# Clock_management.net
KiCad netlist of a schematic drawn in Altium Designer
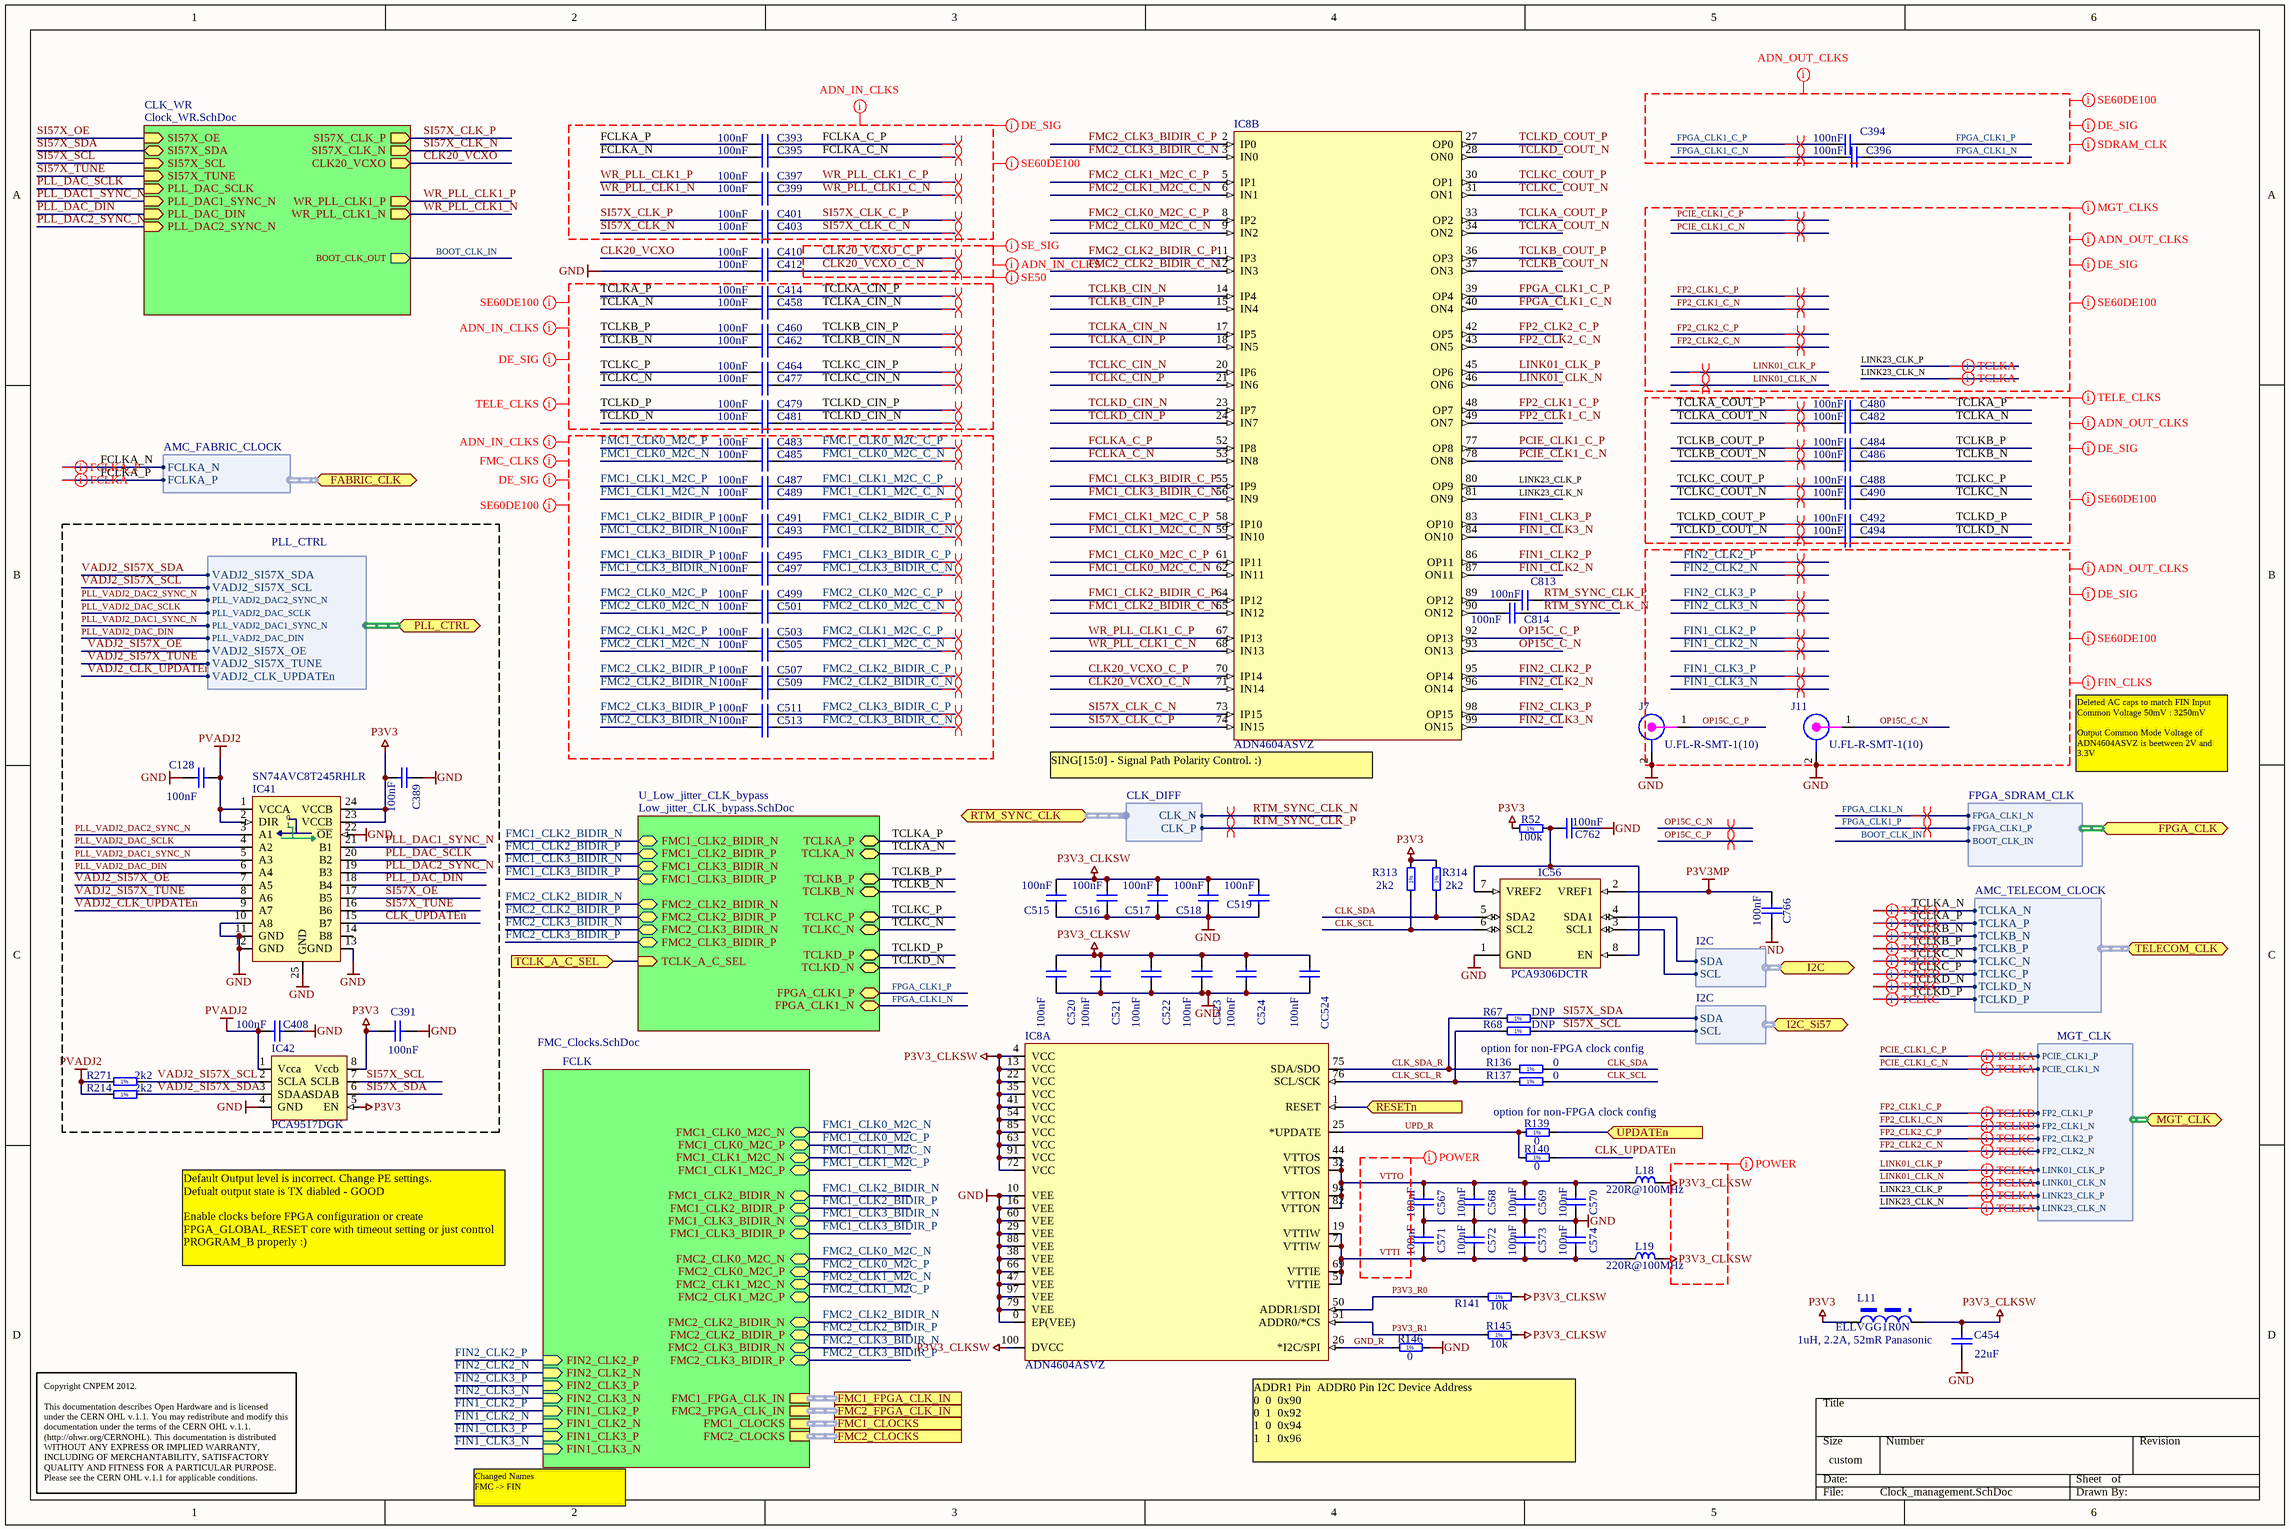
[diagram p0: Clock_management.SchDoc]

(export (version "E")
  (design (tool "Eeschema 10.0.6"))
  (components
    (comp (ref "C128")
      (value "100nF")
      (footprint "CAPC0603X33N")
      (description "Non-polarised capacitor")
      (fields
        (field (name "PART NUMBER") "CC0201_100NF_6.3V_10%_X5R")
        (field (name "VOLTAGE") "6.3V")
        (field (name "AUTHOR") "CERN DEM JLC")
      )
      (libsource (lib "Capacitors") (part "Capacitor - non polarized"))
    )
    (comp (ref "C389")
      (value "100nF")
      (footprint "CAPC0603X33N")
      (description "Non-polarised capacitor")
      (fields
        (field (name "PART NUMBER") "CC0201_100NF_6.3V_10%_X5R")
        (field (name "VOLTAGE") "6.3V")
        (field (name "AUTHOR") "CERN DEM JLC")
      )
      (libsource (lib "Capacitors") (part "Capacitor - non polarized"))
    )
    (comp (ref "C391")
      (value "100nF")
      (footprint "CAPC0603X33N")
      (description "Non-polarised capacitor")
      (fields
        (field (name "PART NUMBER") "CC0201_100NF_6.3V_10%_X5R")
        (field (name "VOLTAGE") "6.3V")
        (field (name "AUTHOR") "CERN DEM JLC")
      )
      (libsource (lib "Capacitors") (part "Capacitor - non polarized"))
    )
    (comp (ref "C393")
      (value "100nF")
      (footprint "CAPC0603X33N")
      (description "Non-polarised capacitor")
      (fields
        (field (name "PART NUMBER") "CC0201_100NF_6.3V_10%_X5R")
        (field (name "VOLTAGE") "6.3V")
        (field (name "AUTHOR") "CERN DEM JLC")
      )
      (libsource (lib "Capacitors") (part "Capacitor - non polarized"))
    )
    (comp (ref "C394")
      (value "100nF")
      (footprint "CAPC0603X33N")
      (description "Non-polarised capacitor")
      (fields
        (field (name "PART NUMBER") "CC0201_100NF_6.3V_10%_X5R")
        (field (name "VOLTAGE") "6.3V")
        (field (name "AUTHOR") "CERN DEM JLC")
      )
      (libsource (lib "Capacitors") (part "Capacitor - non polarized"))
    )
    (comp (ref "C395")
      (value "100nF")
      (footprint "CAPC0603X33N")
      (description "Non-polarised capacitor")
      (fields
        (field (name "PART NUMBER") "CC0201_100NF_6.3V_10%_X5R")
        (field (name "VOLTAGE") "6.3V")
        (field (name "AUTHOR") "CERN DEM JLC")
      )
      (libsource (lib "Capacitors") (part "Capacitor - non polarized"))
    )
    (comp (ref "C396")
      (value "100nF")
      (footprint "CAPC0603X33N")
      (description "Non-polarised capacitor")
      (fields
        (field (name "PART NUMBER") "CC0201_100NF_6.3V_10%_X5R")
        (field (name "VOLTAGE") "6.3V")
        (field (name "AUTHOR") "CERN DEM JLC")
      )
      (libsource (lib "Capacitors") (part "Capacitor - non polarized"))
    )
    (comp (ref "C397")
      (value "100nF")
      (footprint "CAPC0603X33N")
      (description "Non-polarised capacitor")
      (fields
        (field (name "PART NUMBER") "CC0201_100NF_6.3V_10%_X5R")
        (field (name "VOLTAGE") "6.3V")
        (field (name "AUTHOR") "CERN DEM JLC")
      )
      (libsource (lib "Capacitors") (part "Capacitor - non polarized"))
    )
    (comp (ref "C399")
      (value "100nF")
      (footprint "CAPC0603X33N")
      (description "Non-polarised capacitor")
      (fields
        (field (name "PART NUMBER") "CC0201_100NF_6.3V_10%_X5R")
        (field (name "VOLTAGE") "6.3V")
        (field (name "AUTHOR") "CERN DEM JLC")
      )
      (libsource (lib "Capacitors") (part "Capacitor - non polarized"))
    )
    (comp (ref "C401")
      (value "100nF")
      (footprint "CAPC0603X33N")
      (description "Non-polarised capacitor")
      (fields
        (field (name "PART NUMBER") "CC0201_100NF_6.3V_10%_X5R")
        (field (name "VOLTAGE") "6.3V")
        (field (name "AUTHOR") "CERN DEM JLC")
      )
      (libsource (lib "Capacitors") (part "Capacitor - non polarized"))
    )
    (comp (ref "C403")
      (value "100nF")
      (footprint "CAPC0603X33N")
      (description "Non-polarised capacitor")
      (fields
        (field (name "PART NUMBER") "CC0201_100NF_6.3V_10%_X5R")
        (field (name "VOLTAGE") "6.3V")
        (field (name "AUTHOR") "CERN DEM JLC")
      )
      (libsource (lib "Capacitors") (part "Capacitor - non polarized"))
    )
    (comp (ref "C408")
      (value "100nF")
      (footprint "CAPC0603X33N")
      (description "Non-polarised capacitor")
      (fields
        (field (name "PART NUMBER") "CC0201_100NF_6.3V_10%_X5R")
        (field (name "VOLTAGE") "6.3V")
        (field (name "AUTHOR") "CERN DEM JLC")
      )
      (libsource (lib "Capacitors") (part "Capacitor - non polarized"))
    )
    (comp (ref "C410")
      (value "100nF")
      (footprint "CAPC0603X33N")
      (description "Non-polarised capacitor")
      (fields
        (field (name "PART NUMBER") "CC0201_100NF_6.3V_10%_X5R")
        (field (name "VOLTAGE") "6.3V")
        (field (name "AUTHOR") "CERN DEM JLC")
      )
      (libsource (lib "Capacitors") (part "Capacitor - non polarized"))
    )
    (comp (ref "C412")
      (value "100nF")
      (footprint "CAPC0603X33N")
      (description "Non-polarised capacitor")
      (fields
        (field (name "PART NUMBER") "CC0201_100NF_6.3V_10%_X5R")
        (field (name "VOLTAGE") "6.3V")
        (field (name "AUTHOR") "CERN DEM JLC")
      )
      (libsource (lib "Capacitors") (part "Capacitor - non polarized"))
    )
    (comp (ref "C414")
      (value "100nF")
      (footprint "CAPC0603X33N")
      (description "Non-polarised capacitor")
      (fields
        (field (name "PART NUMBER") "CC0201_100NF_6.3V_10%_X5R")
        (field (name "VOLTAGE") "6.3V")
        (field (name "AUTHOR") "CERN DEM JLC")
      )
      (libsource (lib "Capacitors") (part "Capacitor - non polarized"))
    )
    (comp (ref "C454")
      (value "22uF")
      (footprint "CAPC3216X180N")
      (description "Non-polarised capacitor")
      (fields
        (field (name "PART NUMBER") "CC1206_22UF_10V_10%_X7R")
        (field (name "VOLTAGE") "10V")
        (field (name "AUTHOR") "CERN DEM JLC")
      )
      (libsource (lib "Capacitors") (part "Capacitor - non polarized"))
    )
    (comp (ref "C458")
      (value "100nF")
      (footprint "CAPC0603X33N")
      (description "Non-polarised capacitor")
      (fields
        (field (name "PART NUMBER") "CC0201_100NF_6.3V_10%_X5R")
        (field (name "VOLTAGE") "6.3V")
        (field (name "AUTHOR") "CERN DEM JLC")
      )
      (libsource (lib "Capacitors") (part "Capacitor - non polarized"))
    )
    (comp (ref "C460")
      (value "100nF")
      (footprint "CAPC0603X33N")
      (description "Non-polarised capacitor")
      (fields
        (field (name "PART NUMBER") "CC0201_100NF_6.3V_10%_X5R")
        (field (name "VOLTAGE") "6.3V")
        (field (name "AUTHOR") "CERN DEM JLC")
      )
      (libsource (lib "Capacitors") (part "Capacitor - non polarized"))
    )
    (comp (ref "C462")
      (value "100nF")
      (footprint "CAPC0603X33N")
      (description "Non-polarised capacitor")
      (fields
        (field (name "PART NUMBER") "CC0201_100NF_6.3V_10%_X5R")
        (field (name "VOLTAGE") "6.3V")
        (field (name "AUTHOR") "CERN DEM JLC")
      )
      (libsource (lib "Capacitors") (part "Capacitor - non polarized"))
    )
    (comp (ref "C464")
      (value "100nF")
      (footprint "CAPC0603X33N")
      (description "Non-polarised capacitor")
      (fields
        (field (name "PART NUMBER") "CC0201_100NF_6.3V_10%_X5R")
        (field (name "VOLTAGE") "6.3V")
        (field (name "AUTHOR") "CERN DEM JLC")
      )
      (libsource (lib "Capacitors") (part "Capacitor - non polarized"))
    )
    (comp (ref "C477")
      (value "100nF")
      (footprint "CAPC0603X33N")
      (description "Non-polarised capacitor")
      (fields
        (field (name "PART NUMBER") "CC0201_100NF_6.3V_10%_X5R")
        (field (name "VOLTAGE") "6.3V")
        (field (name "AUTHOR") "CERN DEM JLC")
      )
      (libsource (lib "Capacitors") (part "Capacitor - non polarized"))
    )
    (comp (ref "C479")
      (value "100nF")
      (footprint "CAPC0603X33N")
      (description "Non-polarised capacitor")
      (fields
        (field (name "PART NUMBER") "CC0201_100NF_6.3V_10%_X5R")
        (field (name "VOLTAGE") "6.3V")
        (field (name "AUTHOR") "CERN DEM JLC")
      )
      (libsource (lib "Capacitors") (part "Capacitor - non polarized"))
    )
    (comp (ref "C480")
      (value "100nF")
      (footprint "CAPC0603X33N")
      (description "Non-polarised capacitor")
      (fields
        (field (name "PART NUMBER") "CC0201_100NF_6.3V_10%_X5R")
        (field (name "VOLTAGE") "6.3V")
        (field (name "AUTHOR") "CERN DEM JLC")
      )
      (libsource (lib "Capacitors") (part "Capacitor - non polarized"))
    )
    (comp (ref "C481")
      (value "100nF")
      (footprint "CAPC0603X33N")
      (description "Non-polarised capacitor")
      (fields
        (field (name "PART NUMBER") "CC0201_100NF_6.3V_10%_X5R")
        (field (name "VOLTAGE") "6.3V")
        (field (name "AUTHOR") "CERN DEM JLC")
      )
      (libsource (lib "Capacitors") (part "Capacitor - non polarized"))
    )
    (comp (ref "C482")
      (value "100nF")
      (footprint "CAPC0603X33N")
      (description "Non-polarised capacitor")
      (fields
        (field (name "PART NUMBER") "CC0201_100NF_6.3V_10%_X5R")
        (field (name "VOLTAGE") "6.3V")
        (field (name "AUTHOR") "CERN DEM JLC")
      )
      (libsource (lib "Capacitors") (part "Capacitor - non polarized"))
    )
    (comp (ref "C483")
      (value "100nF")
      (footprint "CAPC0603X33N")
      (description "Non-polarised capacitor")
      (fields
        (field (name "PART NUMBER") "CC0201_100NF_6.3V_10%_X5R")
        (field (name "VOLTAGE") "6.3V")
        (field (name "AUTHOR") "CERN DEM JLC")
      )
      (libsource (lib "Capacitors") (part "Capacitor - non polarized"))
    )
    (comp (ref "C484")
      (value "100nF")
      (footprint "CAPC0603X33N")
      (description "Non-polarised capacitor")
      (fields
        (field (name "PART NUMBER") "CC0201_100NF_6.3V_10%_X5R")
        (field (name "VOLTAGE") "6.3V")
        (field (name "AUTHOR") "CERN DEM JLC")
      )
      (libsource (lib "Capacitors") (part "Capacitor - non polarized"))
    )
    (comp (ref "C485")
      (value "100nF")
      (footprint "CAPC0603X33N")
      (description "Non-polarised capacitor")
      (fields
        (field (name "PART NUMBER") "CC0201_100NF_6.3V_10%_X5R")
        (field (name "VOLTAGE") "6.3V")
        (field (name "AUTHOR") "CERN DEM JLC")
      )
      (libsource (lib "Capacitors") (part "Capacitor - non polarized"))
    )
    (comp (ref "C486")
      (value "100nF")
      (footprint "CAPC0603X33N")
      (description "Non-polarised capacitor")
      (fields
        (field (name "PART NUMBER") "CC0201_100NF_6.3V_10%_X5R")
        (field (name "VOLTAGE") "6.3V")
        (field (name "AUTHOR") "CERN DEM JLC")
      )
      (libsource (lib "Capacitors") (part "Capacitor - non polarized"))
    )
    (comp (ref "C487")
      (value "100nF")
      (footprint "CAPC0603X33N")
      (description "Non-polarised capacitor")
      (fields
        (field (name "PART NUMBER") "CC0201_100NF_6.3V_10%_X5R")
        (field (name "VOLTAGE") "6.3V")
        (field (name "AUTHOR") "CERN DEM JLC")
      )
      (libsource (lib "Capacitors") (part "Capacitor - non polarized"))
    )
    (comp (ref "C488")
      (value "100nF")
      (footprint "CAPC0603X33N")
      (description "Non-polarised capacitor")
      (fields
        (field (name "PART NUMBER") "CC0201_100NF_6.3V_10%_X5R")
        (field (name "VOLTAGE") "6.3V")
        (field (name "AUTHOR") "CERN DEM JLC")
      )
      (libsource (lib "Capacitors") (part "Capacitor - non polarized"))
    )
    (comp (ref "C489")
      (value "100nF")
      (footprint "CAPC0603X33N")
      (description "Non-polarised capacitor")
      (fields
        (field (name "PART NUMBER") "CC0201_100NF_6.3V_10%_X5R")
        (field (name "VOLTAGE") "6.3V")
        (field (name "AUTHOR") "CERN DEM JLC")
      )
      (libsource (lib "Capacitors") (part "Capacitor - non polarized"))
    )
    (comp (ref "C490")
      (value "100nF")
      (footprint "CAPC0603X33N")
      (description "Non-polarised capacitor")
      (fields
        (field (name "PART NUMBER") "CC0201_100NF_6.3V_10%_X5R")
        (field (name "VOLTAGE") "6.3V")
        (field (name "AUTHOR") "CERN DEM JLC")
      )
      (libsource (lib "Capacitors") (part "Capacitor - non polarized"))
    )
    (comp (ref "C491")
      (value "100nF")
      (footprint "CAPC0603X33N")
      (description "Non-polarised capacitor")
      (fields
        (field (name "PART NUMBER") "CC0201_100NF_6.3V_10%_X5R")
        (field (name "VOLTAGE") "6.3V")
        (field (name "AUTHOR") "CERN DEM JLC")
      )
      (libsource (lib "Capacitors") (part "Capacitor - non polarized"))
    )
    (comp (ref "C492")
      (value "100nF")
      (footprint "CAPC0603X33N")
      (description "Non-polarised capacitor")
      (fields
        (field (name "PART NUMBER") "CC0201_100NF_6.3V_10%_X5R")
        (field (name "VOLTAGE") "6.3V")
        (field (name "AUTHOR") "CERN DEM JLC")
      )
      (libsource (lib "Capacitors") (part "Capacitor - non polarized"))
    )
    (comp (ref "C493")
      (value "100nF")
      (footprint "CAPC0603X33N")
      (description "Non-polarised capacitor")
      (fields
        (field (name "PART NUMBER") "CC0201_100NF_6.3V_10%_X5R")
        (field (name "VOLTAGE") "6.3V")
        (field (name "AUTHOR") "CERN DEM JLC")
      )
      (libsource (lib "Capacitors") (part "Capacitor - non polarized"))
    )
    (comp (ref "C494")
      (value "100nF")
      (footprint "CAPC0603X33N")
      (description "Non-polarised capacitor")
      (fields
        (field (name "PART NUMBER") "CC0201_100NF_6.3V_10%_X5R")
        (field (name "VOLTAGE") "6.3V")
        (field (name "AUTHOR") "CERN DEM JLC")
      )
      (libsource (lib "Capacitors") (part "Capacitor - non polarized"))
    )
    (comp (ref "C495")
      (value "100nF")
      (footprint "CAPC0603X33N")
      (description "Non-polarised capacitor")
      (fields
        (field (name "PART NUMBER") "CC0201_100NF_6.3V_10%_X5R")
        (field (name "VOLTAGE") "6.3V")
        (field (name "AUTHOR") "CERN DEM JLC")
      )
      (libsource (lib "Capacitors") (part "Capacitor - non polarized"))
    )
    (comp (ref "C497")
      (value "100nF")
      (footprint "CAPC0603X33N")
      (description "Non-polarised capacitor")
      (fields
        (field (name "PART NUMBER") "CC0201_100NF_6.3V_10%_X5R")
        (field (name "VOLTAGE") "6.3V")
        (field (name "AUTHOR") "CERN DEM JLC")
      )
      (libsource (lib "Capacitors") (part "Capacitor - non polarized"))
    )
    (comp (ref "C499")
      (value "100nF")
      (footprint "CAPC0603X33N")
      (description "Non-polarised capacitor")
      (fields
        (field (name "PART NUMBER") "CC0201_100NF_6.3V_10%_X5R")
        (field (name "VOLTAGE") "6.3V")
        (field (name "AUTHOR") "CERN DEM JLC")
      )
      (libsource (lib "Capacitors") (part "Capacitor - non polarized"))
    )
    (comp (ref "C501")
      (value "100nF")
      (footprint "CAPC0603X33N")
      (description "Non-polarised capacitor")
      (fields
        (field (name "PART NUMBER") "CC0201_100NF_6.3V_10%_X5R")
        (field (name "VOLTAGE") "6.3V")
        (field (name "AUTHOR") "CERN DEM JLC")
      )
      (libsource (lib "Capacitors") (part "Capacitor - non polarized"))
    )
    (comp (ref "C503")
      (value "100nF")
      (footprint "CAPC0603X33N")
      (description "Non-polarised capacitor")
      (fields
        (field (name "PART NUMBER") "CC0201_100NF_6.3V_10%_X5R")
        (field (name "VOLTAGE") "6.3V")
        (field (name "AUTHOR") "CERN DEM JLC")
      )
      (libsource (lib "Capacitors") (part "Capacitor - non polarized"))
    )
    (comp (ref "C505")
      (value "100nF")
      (footprint "CAPC0603X33N")
      (description "Non-polarised capacitor")
      (fields
        (field (name "PART NUMBER") "CC0201_100NF_6.3V_10%_X5R")
        (field (name "VOLTAGE") "6.3V")
        (field (name "AUTHOR") "CERN DEM JLC")
      )
      (libsource (lib "Capacitors") (part "Capacitor - non polarized"))
    )
    (comp (ref "C507")
      (value "100nF")
      (footprint "CAPC0603X33N")
      (description "Non-polarised capacitor")
      (fields
        (field (name "PART NUMBER") "CC0201_100NF_6.3V_10%_X5R")
        (field (name "VOLTAGE") "6.3V")
        (field (name "AUTHOR") "CERN DEM JLC")
      )
      (libsource (lib "Capacitors") (part "Capacitor - non polarized"))
    )
    (comp (ref "C509")
      (value "100nF")
      (footprint "CAPC0603X33N")
      (description "Non-polarised capacitor")
      (fields
        (field (name "PART NUMBER") "CC0201_100NF_6.3V_10%_X5R")
        (field (name "VOLTAGE") "6.3V")
        (field (name "AUTHOR") "CERN DEM JLC")
      )
      (libsource (lib "Capacitors") (part "Capacitor - non polarized"))
    )
    (comp (ref "C511")
      (value "100nF")
      (footprint "CAPC0603X33N")
      (description "Non-polarised capacitor")
      (fields
        (field (name "PART NUMBER") "CC0201_100NF_6.3V_10%_X5R")
        (field (name "VOLTAGE") "6.3V")
        (field (name "AUTHOR") "CERN DEM JLC")
      )
      (libsource (lib "Capacitors") (part "Capacitor - non polarized"))
    )
    (comp (ref "C513")
      (value "100nF")
      (footprint "CAPC0603X33N")
      (description "Non-polarised capacitor")
      (fields
        (field (name "PART NUMBER") "CC0201_100NF_6.3V_10%_X5R")
        (field (name "VOLTAGE") "6.3V")
        (field (name "AUTHOR") "CERN DEM JLC")
      )
      (libsource (lib "Capacitors") (part "Capacitor - non polarized"))
    )
    (comp (ref "C515")
      (value "100nF")
      (footprint "CAPC0603X33N")
      (description "Non-polarised capacitor")
      (fields
        (field (name "PART NUMBER") "CC0201_100NF_6.3V_10%_X5R")
        (field (name "VOLTAGE") "6.3V")
        (field (name "AUTHOR") "CERN DEM JLC")
      )
      (libsource (lib "Capacitors") (part "Capacitor - non polarized"))
    )
    (comp (ref "C516")
      (value "100nF")
      (footprint "CAPC0603X33N")
      (description "Non-polarised capacitor")
      (fields
        (field (name "PART NUMBER") "CC0201_100NF_6.3V_10%_X5R")
        (field (name "VOLTAGE") "6.3V")
        (field (name "AUTHOR") "CERN DEM JLC")
      )
      (libsource (lib "Capacitors") (part "Capacitor - non polarized"))
    )
    (comp (ref "C517")
      (value "100nF")
      (footprint "CAPC0603X33N")
      (description "Non-polarised capacitor")
      (fields
        (field (name "PART NUMBER") "CC0201_100NF_6.3V_10%_X5R")
        (field (name "VOLTAGE") "6.3V")
        (field (name "AUTHOR") "CERN DEM JLC")
      )
      (libsource (lib "Capacitors") (part "Capacitor - non polarized"))
    )
    (comp (ref "C518")
      (value "100nF")
      (footprint "CAPC0603X33N")
      (description "Non-polarised capacitor")
      (fields
        (field (name "PART NUMBER") "CC0201_100NF_6.3V_10%_X5R")
        (field (name "VOLTAGE") "6.3V")
        (field (name "AUTHOR") "CERN DEM JLC")
      )
      (libsource (lib "Capacitors") (part "Capacitor - non polarized"))
    )
    (comp (ref "C519")
      (value "100nF")
      (footprint "CAPC0603X33N")
      (description "Non-polarised capacitor")
      (fields
        (field (name "PART NUMBER") "CC0201_100NF_6.3V_10%_X5R")
        (field (name "VOLTAGE") "6.3V")
        (field (name "AUTHOR") "CERN DEM JLC")
      )
      (libsource (lib "Capacitors") (part "Capacitor - non polarized"))
    )
    (comp (ref "C520")
      (value "100nF")
      (footprint "CAPC0603X33N")
      (description "Non-polarised capacitor")
      (fields
        (field (name "PART NUMBER") "CC0201_100NF_6.3V_10%_X5R")
        (field (name "VOLTAGE") "6.3V")
        (field (name "AUTHOR") "CERN DEM JLC")
      )
      (libsource (lib "Capacitors") (part "Capacitor - non polarized"))
    )
    (comp (ref "C521")
      (value "100nF")
      (footprint "CAPC0603X33N")
      (description "Non-polarised capacitor")
      (fields
        (field (name "PART NUMBER") "CC0201_100NF_6.3V_10%_X5R")
        (field (name "VOLTAGE") "6.3V")
        (field (name "AUTHOR") "CERN DEM JLC")
      )
      (libsource (lib "Capacitors") (part "Capacitor - non polarized"))
    )
    (comp (ref "C522")
      (value "100nF")
      (footprint "CAPC0603X33N")
      (description "Non-polarised capacitor")
      (fields
        (field (name "PART NUMBER") "CC0201_100NF_6.3V_10%_X5R")
        (field (name "VOLTAGE") "6.3V")
        (field (name "AUTHOR") "CERN DEM JLC")
      )
      (libsource (lib "Capacitors") (part "Capacitor - non polarized"))
    )
    (comp (ref "C523")
      (value "100nF")
      (footprint "CAPC0603X33N")
      (description "Non-polarised capacitor")
      (fields
        (field (name "PART NUMBER") "CC0201_100NF_6.3V_10%_X5R")
        (field (name "VOLTAGE") "6.3V")
        (field (name "AUTHOR") "CERN DEM JLC")
      )
      (libsource (lib "Capacitors") (part "Capacitor - non polarized"))
    )
    (comp (ref "C524")
      (value "100nF")
      (footprint "CAPC0603X33N")
      (description "Non-polarised capacitor")
      (fields
        (field (name "PART NUMBER") "CC0201_100NF_6.3V_10%_X5R")
        (field (name "VOLTAGE") "6.3V")
        (field (name "AUTHOR") "CERN DEM JLC")
      )
      (libsource (lib "Capacitors") (part "Capacitor - non polarized"))
    )
    (comp (ref "C567")
      (value "100nF")
      (footprint "CAPC0603X33N")
      (description "Non-polarised capacitor")
      (fields
        (field (name "PART NUMBER") "CC0201_100NF_6.3V_10%_X5R")
        (field (name "VOLTAGE") "6.3V")
        (field (name "AUTHOR") "CERN DEM JLC")
      )
      (libsource (lib "Capacitors") (part "Capacitor - non polarized"))
    )
    (comp (ref "C568")
      (value "100nF")
      (footprint "CAPC0603X33N")
      (description "Non-polarised capacitor")
      (fields
        (field (name "PART NUMBER") "CC0201_100NF_6.3V_10%_X5R")
        (field (name "VOLTAGE") "6.3V")
        (field (name "AUTHOR") "CERN DEM JLC")
      )
      (libsource (lib "Capacitors") (part "Capacitor - non polarized"))
    )
    (comp (ref "C569")
      (value "100nF")
      (footprint "CAPC0603X33N")
      (description "Non-polarised capacitor")
      (fields
        (field (name "PART NUMBER") "CC0201_100NF_6.3V_10%_X5R")
        (field (name "VOLTAGE") "6.3V")
        (field (name "AUTHOR") "CERN DEM JLC")
      )
      (libsource (lib "Capacitors") (part "Capacitor - non polarized"))
    )
    (comp (ref "C570")
      (value "100nF")
      (footprint "CAPC0603X33N")
      (description "Non-polarised capacitor")
      (fields
        (field (name "PART NUMBER") "CC0201_100NF_6.3V_10%_X5R")
        (field (name "VOLTAGE") "6.3V")
        (field (name "AUTHOR") "CERN DEM JLC")
      )
      (libsource (lib "Capacitors") (part "Capacitor - non polarized"))
    )
    (comp (ref "C571")
      (value "100nF")
      (footprint "CAPC0603X33N")
      (description "Non-polarised capacitor")
      (fields
        (field (name "PART NUMBER") "CC0201_100NF_6.3V_10%_X5R")
        (field (name "VOLTAGE") "6.3V")
        (field (name "AUTHOR") "CERN DEM JLC")
      )
      (libsource (lib "Capacitors") (part "Capacitor - non polarized"))
    )
    (comp (ref "C572")
      (value "100nF")
      (footprint "CAPC0603X33N")
      (description "Non-polarised capacitor")
      (fields
        (field (name "PART NUMBER") "CC0201_100NF_6.3V_10%_X5R")
        (field (name "VOLTAGE") "6.3V")
        (field (name "AUTHOR") "CERN DEM JLC")
      )
      (libsource (lib "Capacitors") (part "Capacitor - non polarized"))
    )
    (comp (ref "C573")
      (value "100nF")
      (footprint "CAPC0603X33N")
      (description "Non-polarised capacitor")
      (fields
        (field (name "PART NUMBER") "CC0201_100NF_6.3V_10%_X5R")
        (field (name "VOLTAGE") "6.3V")
        (field (name "AUTHOR") "CERN DEM JLC")
      )
      (libsource (lib "Capacitors") (part "Capacitor - non polarized"))
    )
    (comp (ref "C574")
      (value "100nF")
      (footprint "CAPC0603X33N")
      (description "Non-polarised capacitor")
      (fields
        (field (name "PART NUMBER") "CC0201_100NF_6.3V_10%_X5R")
        (field (name "VOLTAGE") "6.3V")
        (field (name "AUTHOR") "CERN DEM JLC")
      )
      (libsource (lib "Capacitors") (part "Capacitor - non polarized"))
    )
    (comp (ref "C762")
      (value "100nF")
      (footprint "CAPC0603X33N")
      (description "Non-polarised capacitor")
      (fields
        (field (name "PART NUMBER") "CC0201_100NF_6.3V_10%_X5R")
        (field (name "VOLTAGE") "6.3V")
        (field (name "AUTHOR") "CERN DEM JLC")
      )
      (libsource (lib "Capacitors") (part "Capacitor - non polarized"))
    )
    (comp (ref "C766")
      (value "100nF")
      (footprint "CAPC0603X33N")
      (description "Non-polarised capacitor")
      (fields
        (field (name "PART NUMBER") "CC0201_100NF_6.3V_10%_X5R")
        (field (name "VOLTAGE") "6.3V")
        (field (name "AUTHOR") "CERN DEM JLC")
      )
      (libsource (lib "Capacitors") (part "Capacitor - non polarized"))
    )
    (comp (ref "C813")
      (value "100nF")
      (footprint "CAPC0603X33N")
      (description "Non-polarised capacitor")
      (fields
        (field (name "PART NUMBER") "CC0201_100NF_6.3V_10%_X5R")
        (field (name "VOLTAGE") "6.3V")
        (field (name "AUTHOR") "CERN DEM JLC")
      )
      (libsource (lib "Capacitors") (part "Capacitor - non polarized"))
    )
    (comp (ref "C814")
      (value "100nF")
      (footprint "CAPC0603X33N")
      (description "Non-polarised capacitor")
      (fields
        (field (name "PART NUMBER") "CC0201_100NF_6.3V_10%_X5R")
        (field (name "VOLTAGE") "6.3V")
        (field (name "AUTHOR") "CERN DEM JLC")
      )
      (libsource (lib "Capacitors") (part "Capacitor - non polarized"))
    )
    (comp (ref "CC524")
      (value "100nF")
      (footprint "CAPC0603X33N")
      (description "Non-polarised capacitor")
      (fields
        (field (name "PART NUMBER") "CC0201_100NF_6.3V_10%_X5R")
        (field (name "VOLTAGE") "6.3V")
        (field (name "AUTHOR") "CERN DEM JLC")
      )
      (libsource (lib "Capacitors") (part "Capacitor - non polarized"))
    )
    (comp (ref "IC8")
      (value "ADN4604ASVZ")
      (footprint "TQFP100_TP")
      (description "16x16 CML crosspoint switch")
      (libsource (lib "") (part "IFC_ADN4604ASVZ_1"))
    )
    (comp (ref "IC41")
      (value "SN74AVC8T245RHLR")
      (footprint "QFN50P350X550X100-24N")
      (description "8 channel bidir translator buffer (1.4..3.6V)")
      (libsource (lib "LIBRARY_SCH") (part "74AVC8T245_QFN"))
    )
    (comp (ref "IC42")
      (value "PCA9517DGK")
      (footprint "msop-8")
      (description "LEVEL-TRANSLATING I2C BUS REPEATER")
      (libsource (lib "LIBRARY_SCH") (part "IFC_PCA9517"))
    )
    (comp (ref "IC56")
      (value "PCA9306DCTR")
      (footprint "SOP65P400X130-8N")
      (description "Dual Bidirectional I2C Bus And SMBus Voltage-Level Translator")
      (fields (field (name "MANUFACTURER") "TEXAS INSTRUMENTS") (field (name "AUTHOR") "CERN DEM JLC"))
      (libsource (lib "ICs And Semiconductors") (part "PCA9306DC"))
    )
    (comp (ref "J7")
      (value "U.FL-R-SMT-1(10)")
      (footprint "CON_UFL_HIROSE_RECEPTACLE")
      (description "UFL")
      (libsource (lib "LIBRARY_SCH") (part "CON_UFL_SMD"))
    )
    (comp (ref "J11")
      (value "U.FL-R-SMT-1(10)")
      (footprint "CON_UFL_HIROSE_RECEPTACLE")
      (description "UFL")
      (libsource (lib "LIBRARY_SCH") (part "CON_UFL_SMD"))
    )
    (comp (ref "L11")
      (value "ELLVGG1R0N")
      (footprint "L_ELLVGG2R2N")
      (description "2.2uH, 1.4A, 92mR Panasonic")
      (fields (field (name "ALTIUM_UNNAMED_1") "1uH, 2.2A, 52mR Panasonic"))
      (libsource (lib "LIBRARY_SCH") (part "L_CHOKE_ELLVGG"))
    )
    (comp (ref "L18")
      (value "220R@100MHz")
      (footprint "INDC2012X105N")
      (description "Inductor")
      (fields
        (field (name "PART NUMBER") "IND0805_MURATA_BLM21PG221SN1D")
        (field (name "POWER") "2A")
        (field (name "AUTHOR") "CERN DEM JLC")
      )
      (libsource (lib "Inductors & Transformers") (part "Inductor"))
    )
    (comp (ref "L19")
      (value "220R@100MHz")
      (footprint "INDC2012X105N")
      (description "Inductor")
      (fields
        (field (name "PART NUMBER") "IND0805_MURATA_BLM21PG221SN1D")
        (field (name "POWER") "2A")
        (field (name "AUTHOR") "CERN DEM JLC")
      )
      (libsource (lib "Inductors & Transformers") (part "Inductor"))
    )
    (comp (ref "R52")
      (value "100k")
      (footprint "RESC1005X40N")
      (description "Resistor - 1%")
      (fields
        (field (name "PART NUMBER") "R0402_100K_1%_0.0625W_100PPM")
        (field (name "POWER") "0.0625W")
        (field (name "AUTHOR") "CERN DEM JLC")
      )
      (libsource (lib "Resistors") (part "Resistor - 1%"))
    )
    (comp (ref "R67")
      (value "DNP")
      (footprint "RESC1005X40N")
      (description "Resistor - 1%")
      (fields
        (field (name "PART NUMBER") "R0402_0R_JUMPER")
        (field (name "MANUFACTURER") "GENERIC")
        (field (name "AUTHOR") "CERN DEM JLC")
      )
      (libsource (lib "Resistors") (part "Resistor - 1%"))
    )
    (comp (ref "R68")
      (value "DNP")
      (footprint "RESC1005X40N")
      (description "Resistor - 1%")
      (fields
        (field (name "PART NUMBER") "R0402_0R_JUMPER")
        (field (name "MANUFACTURER") "GENERIC")
        (field (name "AUTHOR") "CERN DEM JLC")
      )
      (libsource (lib "Resistors") (part "Resistor - 1%"))
    )
    (comp (ref "R136")
      (value "0")
      (footprint "RESC1005X40N")
      (description "Resistor - 1%")
      (fields
        (field (name "PART NUMBER") "R0402_0R_JUMPER")
        (field (name "MANUFACTURER") "GENERIC")
        (field (name "AUTHOR") "CERN DEM JLC")
      )
      (libsource (lib "Resistors") (part "Resistor - 1%"))
    )
    (comp (ref "R137")
      (value "0")
      (footprint "RESC1005X40N")
      (description "Resistor - 1%")
      (fields
        (field (name "PART NUMBER") "R0402_0R_JUMPER")
        (field (name "MANUFACTURER") "GENERIC")
        (field (name "AUTHOR") "CERN DEM JLC")
      )
      (libsource (lib "Resistors") (part "Resistor - 1%"))
    )
    (comp (ref "R139")
      (value "0")
      (footprint "RESC1005X40N")
      (description "Resistor - 1%")
      (fields
        (field (name "PART NUMBER") "R0402_0R_JUMPER")
        (field (name "MANUFACTURER") "GENERIC")
        (field (name "AUTHOR") "CERN DEM JLC")
      )
      (libsource (lib "Resistors") (part "Resistor - 1%"))
    )
    (comp (ref "R140")
      (value "0")
      (footprint "RESC1005X40N")
      (description "Resistor - 1%")
      (fields
        (field (name "PART NUMBER") "R0402_0R_JUMPER")
        (field (name "MANUFACTURER") "GENERIC")
        (field (name "AUTHOR") "CERN DEM JLC")
      )
      (libsource (lib "Resistors") (part "Resistor - 1%"))
    )
    (comp (ref "R141")
      (value "10k")
      (footprint "RESC1005X40N")
      (description "Resistor - 1%")
      (fields
        (field (name "PART NUMBER") "R0402_10K_1%_0.0625W_100PPM")
        (field (name "POWER") "0.0625W")
        (field (name "AUTHOR") "CERN DEM JLC")
      )
      (libsource (lib "Resistors") (part "Resistor - 1%"))
    )
    (comp (ref "R145")
      (value "10k")
      (footprint "RESC1005X40N")
      (description "Resistor - 1%")
      (fields
        (field (name "PART NUMBER") "R0402_10K_1%_0.0625W_100PPM")
        (field (name "POWER") "0.0625W")
        (field (name "AUTHOR") "CERN DEM JLC")
      )
      (libsource (lib "Resistors") (part "Resistor - 1%"))
    )
    (comp (ref "R146")
      (value "0")
      (footprint "RESC1005X40N")
      (description "Resistor - 1%")
      (fields
        (field (name "PART NUMBER") "R0402_0R_JUMPER")
        (field (name "MANUFACTURER") "GENERIC")
        (field (name "AUTHOR") "CERN DEM JLC")
      )
      (libsource (lib "Resistors") (part "Resistor - 1%"))
    )
    (comp (ref "R214")
      (value "2k2")
      (footprint "RESC1005X40N")
      (description "Resistor - 1%")
      (fields
        (field (name "PART NUMBER") "R0402_2K2_1%_0.0625W_100PPM")
        (field (name "POWER") "0.0625W")
        (field (name "AUTHOR") "CERN DEM JLC")
      )
      (libsource (lib "Resistors") (part "Resistor - 1%"))
    )
    (comp (ref "R271")
      (value "2k2")
      (footprint "RESC1005X40N")
      (description "Resistor - 1%")
      (fields
        (field (name "PART NUMBER") "R0402_2K2_1%_0.0625W_100PPM")
        (field (name "POWER") "0.0625W")
        (field (name "AUTHOR") "CERN DEM JLC")
      )
      (libsource (lib "Resistors") (part "Resistor - 1%"))
    )
    (comp (ref "R313")
      (value "2k2")
      (footprint "RESC1005X40N")
      (description "Resistor - 1%")
      (fields
        (field (name "PART NUMBER") "R0402_2K2_1%_0.0625W_100PPM")
        (field (name "POWER") "0.0625W")
        (field (name "AUTHOR") "CERN DEM JLC")
      )
      (libsource (lib "Resistors") (part "Resistor - 1%"))
    )
    (comp (ref "R314")
      (value "2k2")
      (footprint "RESC1005X40N")
      (description "Resistor - 1%")
      (fields
        (field (name "PART NUMBER") "R0402_2K2_1%_0.0625W_100PPM")
        (field (name "POWER") "0.0625W")
        (field (name "AUTHOR") "CERN DEM JLC")
      )
      (libsource (lib "Resistors") (part "Resistor - 1%"))
    )
  )
  (nets
    (net (code "13") (name "/CLK20_VCXO") (class "Default")
      (node (ref "C410") (pin "1") (pinfunction "1_1") (pintype "passive"))
    )
    (net (code "14") (name "/CLK20_VCXO_C_N") (class "Default")
      (node (ref "C412") (pin "2") (pinfunction "2_2") (pintype "passive"))
      (node (ref "IC8") (pin "71") (pinfunction "IN14_71") (pintype "input"))
    )
    (net (code "15") (name "/CLK20_VCXO_C_P") (class "Default")
      (node (ref "C410") (pin "2") (pinfunction "2_2") (pintype "passive"))
      (node (ref "IC8") (pin "70") (pinfunction "IP14_70") (pintype "input"))
    )
    (net (code "16") (name "/CLK_SCL") (class "Default")
      (node (ref "IC56") (pin "6") (pinfunction "SCL2_6") (pintype "bidirectional"))
      (node (ref "R137") (pin "2") (pinfunction "2_2") (pintype "passive"))
      (node (ref "R313") (pin "1") (pinfunction "1_1") (pintype "passive"))
    )
    (net (code "17") (name "/CLK_SCL_R") (class "Default")
      (node (ref "IC8") (pin "76") (pinfunction "SCL/SCK_76") (pintype "input"))
      (node (ref "R137") (pin "1") (pinfunction "1_1") (pintype "passive"))
      (node (ref "R68") (pin "1") (pinfunction "1_1") (pintype "passive"))
    )
    (net (code "18") (name "/CLK_SDA") (class "Default")
      (node (ref "IC56") (pin "5") (pinfunction "SDA2_5") (pintype "bidirectional"))
      (node (ref "R136") (pin "2") (pinfunction "2_2") (pintype "passive"))
      (node (ref "R314") (pin "1") (pinfunction "1_1") (pintype "passive"))
    )
    (net (code "19") (name "/CLK_SDA_R") (class "Default")
      (node (ref "IC8") (pin "75") (pinfunction "SDA/SDO_75") (pintype "bidirectional"))
      (node (ref "R136") (pin "1") (pinfunction "1_1") (pintype "passive"))
      (node (ref "R67") (pin "1") (pinfunction "1_1") (pintype "passive"))
    )
    (net (code "20") (name "/CLK_UPDATEn") (class "Default")
      (node (ref "IC41") (pin "15") (pinfunction "B7_15") (pintype "bidirectional"))
      (node (ref "R140") (pin "2") (pinfunction "2_2") (pintype "passive"))
    )
    (net (code "21") (name "/FCLKA_C_N") (class "Default")
      (node (ref "C395") (pin "2") (pinfunction "2_2") (pintype "passive"))
      (node (ref "IC8") (pin "53") (pinfunction "IN8_53") (pintype "input"))
    )
    (net (code "22") (name "/FCLKA_C_P") (class "Default")
      (node (ref "C393") (pin "2") (pinfunction "2_2") (pintype "passive"))
      (node (ref "IC8") (pin "52") (pinfunction "IP8_52") (pintype "input"))
    )
    (net (code "23") (name "/FCLKA_N") (class "Default")
      (node (ref "C395") (pin "1") (pinfunction "1_1") (pintype "passive"))
    )
    (net (code "24") (name "/FCLKA_P") (class "Default")
      (node (ref "C393") (pin "1") (pinfunction "1_1") (pintype "passive"))
    )
    (net (code "25") (name "/FIN1_CLK2_N") (class "Default")
      (node (ref "IC8") (pin "87") (pinfunction "ON11_87") (pintype "output"))
    )
    (net (code "26") (name "/FIN1_CLK2_P") (class "Default")
      (node (ref "IC8") (pin "86") (pinfunction "OP11_86") (pintype "output"))
    )
    (net (code "27") (name "/FIN1_CLK3_N") (class "Default")
      (node (ref "IC8") (pin "84") (pinfunction "ON10_84") (pintype "output"))
    )
    (net (code "28") (name "/FIN1_CLK3_P") (class "Default")
      (node (ref "IC8") (pin "83") (pinfunction "OP10_83") (pintype "output"))
    )
    (net (code "29") (name "/FIN2_CLK2_N") (class "Default")
      (node (ref "IC8") (pin "96") (pinfunction "ON14_96") (pintype "output"))
    )
    (net (code "30") (name "/FIN2_CLK2_P") (class "Default")
      (node (ref "IC8") (pin "95") (pinfunction "OP14_95") (pintype "output"))
    )
    (net (code "31") (name "/FIN2_CLK3_N") (class "Default")
      (node (ref "IC8") (pin "99") (pinfunction "ON15_99") (pintype "output"))
    )
    (net (code "32") (name "/FIN2_CLK3_P") (class "Default")
      (node (ref "IC8") (pin "98") (pinfunction "OP15_98") (pintype "output"))
    )
    (net (code "33") (name "/FMC1_CLK0_M2C_C_N") (class "Default")
      (node (ref "C485") (pin "2") (pinfunction "2_2") (pintype "passive"))
      (node (ref "IC8") (pin "62") (pinfunction "IN11_62") (pintype "input"))
    )
    (net (code "34") (name "/FMC1_CLK0_M2C_C_P") (class "Default")
      (node (ref "C483") (pin "2") (pinfunction "2_2") (pintype "passive"))
      (node (ref "IC8") (pin "61") (pinfunction "IP11_61") (pintype "input"))
    )
    (net (code "35") (name "/FMC1_CLK0_M2C_N") (class "Default")
      (node (ref "C485") (pin "1") (pinfunction "1_1") (pintype "passive"))
    )
    (net (code "36") (name "/FMC1_CLK0_M2C_P") (class "Default")
      (node (ref "C483") (pin "1") (pinfunction "1_1") (pintype "passive"))
    )
    (net (code "37") (name "/FMC1_CLK1_M2C_C_N") (class "Default")
      (node (ref "C489") (pin "2") (pinfunction "2_2") (pintype "passive"))
      (node (ref "IC8") (pin "59") (pinfunction "IN10_59") (pintype "input"))
    )
    (net (code "38") (name "/FMC1_CLK1_M2C_C_P") (class "Default")
      (node (ref "C487") (pin "2") (pinfunction "2_2") (pintype "passive"))
      (node (ref "IC8") (pin "58") (pinfunction "IP10_58") (pintype "input"))
    )
    (net (code "39") (name "/FMC1_CLK1_M2C_N") (class "Default")
      (node (ref "C489") (pin "1") (pinfunction "1_1") (pintype "passive"))
    )
    (net (code "40") (name "/FMC1_CLK1_M2C_P") (class "Default")
      (node (ref "C487") (pin "1") (pinfunction "1_1") (pintype "passive"))
    )
    (net (code "41") (name "/FMC1_CLK2_BIDIR_C_N") (class "Default")
      (node (ref "C493") (pin "2") (pinfunction "2_2") (pintype "passive"))
      (node (ref "IC8") (pin "65") (pinfunction "IN12_65") (pintype "input"))
    )
    (net (code "42") (name "/FMC1_CLK2_BIDIR_C_P") (class "Default")
      (node (ref "C491") (pin "2") (pinfunction "2_2") (pintype "passive"))
      (node (ref "IC8") (pin "64") (pinfunction "IP12_64") (pintype "input"))
    )
    (net (code "43") (name "/FMC1_CLK2_BIDIR_N") (class "Default")
      (node (ref "C493") (pin "1") (pinfunction "1_1") (pintype "passive"))
    )
    (net (code "44") (name "/FMC1_CLK2_BIDIR_P") (class "Default")
      (node (ref "C491") (pin "1") (pinfunction "1_1") (pintype "passive"))
    )
    (net (code "45") (name "/FMC1_CLK3_BIDIR_C_N") (class "Default")
      (node (ref "C497") (pin "2") (pinfunction "2_2") (pintype "passive"))
      (node (ref "IC8") (pin "56") (pinfunction "IN9_56") (pintype "input"))
    )
    (net (code "46") (name "/FMC1_CLK3_BIDIR_C_P") (class "Default")
      (node (ref "C495") (pin "2") (pinfunction "2_2") (pintype "passive"))
      (node (ref "IC8") (pin "55") (pinfunction "IP9_55") (pintype "input"))
    )
    (net (code "47") (name "/FMC1_CLK3_BIDIR_N") (class "Default")
      (node (ref "C497") (pin "1") (pinfunction "1_1") (pintype "passive"))
    )
    (net (code "48") (name "/FMC1_CLK3_BIDIR_P") (class "Default")
      (node (ref "C495") (pin "1") (pinfunction "1_1") (pintype "passive"))
    )
    (net (code "51") (name "/FMC2_CLK0_M2C_C_N") (class "Default")
      (node (ref "C501") (pin "2") (pinfunction "2_2") (pintype "passive"))
      (node (ref "IC8") (pin "9") (pinfunction "IN2_9") (pintype "input"))
    )
    (net (code "52") (name "/FMC2_CLK0_M2C_C_P") (class "Default")
      (node (ref "C499") (pin "2") (pinfunction "2_2") (pintype "passive"))
      (node (ref "IC8") (pin "8") (pinfunction "IP2_8") (pintype "input"))
    )
    (net (code "53") (name "/FMC2_CLK0_M2C_N") (class "Default")
      (node (ref "C501") (pin "1") (pinfunction "1_1") (pintype "passive"))
    )
    (net (code "54") (name "/FMC2_CLK0_M2C_P") (class "Default")
      (node (ref "C499") (pin "1") (pinfunction "1_1") (pintype "passive"))
    )
    (net (code "55") (name "/FMC2_CLK1_M2C_C_N") (class "Default")
      (node (ref "C505") (pin "2") (pinfunction "2_2") (pintype "passive"))
      (node (ref "IC8") (pin "6") (pinfunction "IN1_6") (pintype "input"))
    )
    (net (code "56") (name "/FMC2_CLK1_M2C_C_P") (class "Default")
      (node (ref "C503") (pin "2") (pinfunction "2_2") (pintype "passive"))
      (node (ref "IC8") (pin "5") (pinfunction "IP1_5") (pintype "input"))
    )
    (net (code "57") (name "/FMC2_CLK1_M2C_N") (class "Default")
      (node (ref "C505") (pin "1") (pinfunction "1_1") (pintype "passive"))
    )
    (net (code "58") (name "/FMC2_CLK1_M2C_P") (class "Default")
      (node (ref "C503") (pin "1") (pinfunction "1_1") (pintype "passive"))
    )
    (net (code "59") (name "/FMC2_CLK2_BIDIR_C_N") (class "Default")
      (node (ref "C509") (pin "2") (pinfunction "2_2") (pintype "passive"))
      (node (ref "IC8") (pin "12") (pinfunction "IN3_12") (pintype "input"))
    )
    (net (code "60") (name "/FMC2_CLK2_BIDIR_C_P") (class "Default")
      (node (ref "C507") (pin "2") (pinfunction "2_2") (pintype "passive"))
      (node (ref "IC8") (pin "11") (pinfunction "IP3_11") (pintype "input"))
    )
    (net (code "61") (name "/FMC2_CLK2_BIDIR_N") (class "Default")
      (node (ref "C509") (pin "1") (pinfunction "1_1") (pintype "passive"))
    )
    (net (code "62") (name "/FMC2_CLK2_BIDIR_P") (class "Default")
      (node (ref "C507") (pin "1") (pinfunction "1_1") (pintype "passive"))
    )
    (net (code "63") (name "/FMC2_CLK3_BIDIR_C_N") (class "Default")
      (node (ref "C513") (pin "2") (pinfunction "2_2") (pintype "passive"))
      (node (ref "IC8") (pin "3") (pinfunction "IN0_3") (pintype "input"))
    )
    (net (code "64") (name "/FMC2_CLK3_BIDIR_C_P") (class "Default")
      (node (ref "C511") (pin "2") (pinfunction "2_2") (pintype "passive"))
      (node (ref "IC8") (pin "2") (pinfunction "IP0_2") (pintype "input"))
    )
    (net (code "65") (name "/FMC2_CLK3_BIDIR_N") (class "Default")
      (node (ref "C513") (pin "1") (pinfunction "1_1") (pintype "passive"))
    )
    (net (code "66") (name "/FMC2_CLK3_BIDIR_P") (class "Default")
      (node (ref "C511") (pin "1") (pinfunction "1_1") (pintype "passive"))
    )
    (net (code "69") (name "/FP2_CLK1_C_N") (class "Default")
      (node (ref "IC8") (pin "49") (pinfunction "ON7_49") (pintype "output"))
    )
    (net (code "70") (name "/FP2_CLK1_C_P") (class "Default")
      (node (ref "IC8") (pin "48") (pinfunction "OP7_48") (pintype "output"))
    )
    (net (code "71") (name "/FP2_CLK2_C_N") (class "Default")
      (node (ref "IC8") (pin "43") (pinfunction "ON5_43") (pintype "output"))
    )
    (net (code "72") (name "/FP2_CLK2_C_P") (class "Default")
      (node (ref "IC8") (pin "42") (pinfunction "OP5_42") (pintype "output"))
    )
    (net (code "73") (name "/FPGA_CLK1_C_N") (class "Default")
      (node (ref "C396") (pin "1") (pinfunction "1_1") (pintype "passive"))
      (node (ref "IC8") (pin "40") (pinfunction "ON4_40") (pintype "output"))
    )
    (net (code "74") (name "/FPGA_CLK1_C_P") (class "Default")
      (node (ref "C394") (pin "1") (pinfunction "1_1") (pintype "passive"))
      (node (ref "IC8") (pin "39") (pinfunction "OP4_39") (pintype "output"))
    )
    (net (code "75") (name "/FPGA_CLK1_N") (class "Default")
      (node (ref "C396") (pin "2") (pinfunction "2_2") (pintype "passive"))
    )
    (net (code "76") (name "/FPGA_CLK1_P") (class "Default")
      (node (ref "C394") (pin "2") (pinfunction "2_2") (pintype "passive"))
    )
    (net (code "77") (name "/GND_R") (class "Default")
      (node (ref "IC8") (pin "26") (pinfunction "*I2C/SPI_26") (pintype "input"))
      (node (ref "R146") (pin "1") (pinfunction "1_1") (pintype "passive"))
    )
    (net (code "78") (name "/LINK01_CLK_N") (class "Default")
      (node (ref "IC8") (pin "46") (pinfunction "ON6_46") (pintype "output"))
    )
    (net (code "79") (name "/LINK01_CLK_P") (class "Default")
      (node (ref "IC8") (pin "45") (pinfunction "OP6_45") (pintype "output"))
    )
    (net (code "80") (name "/LINK23_CLK_N") (class "Default")
      (node (ref "IC8") (pin "81") (pinfunction "ON9_81") (pintype "output"))
    )
    (net (code "81") (name "/LINK23_CLK_P") (class "Default")
      (node (ref "IC8") (pin "80") (pinfunction "OP9_80") (pintype "output"))
    )
    (net (code "82") (name "/OP15C_C_N") (class "Default")
      (node (ref "IC8") (pin "93") (pinfunction "ON13_93") (pintype "output"))
      (node (ref "J11") (pin "1") (pintype "passive"))
    )
    (net (code "83") (name "/OP15C_C_P") (class "Default")
      (node (ref "IC8") (pin "92") (pinfunction "OP13_92") (pintype "output"))
      (node (ref "J7") (pin "1") (pintype "passive"))
    )
    (net (code "84") (name "/P3V3_R0") (class "Default")
      (node (ref "IC8") (pin "50") (pinfunction "ADDR1/SDI_50") (pintype "input"))
      (node (ref "R141") (pin "1") (pinfunction "1_1") (pintype "passive"))
    )
    (net (code "85") (name "/P3V3_R1") (class "Default")
      (node (ref "IC8") (pin "51") (pinfunction "ADDR0/*CS_51") (pintype "input"))
      (node (ref "R145") (pin "1") (pinfunction "1_1") (pintype "passive"))
    )
    (net (code "86") (name "/PCIE_CLK1_C_N") (class "Default")
      (node (ref "IC8") (pin "78") (pinfunction "ON8_78") (pintype "output"))
    )
    (net (code "87") (name "/PCIE_CLK1_C_P") (class "Default")
      (node (ref "IC8") (pin "77") (pinfunction "OP8_77") (pintype "output"))
    )
    (net (code "88") (name "/PLL_DAC1_SYNC_N") (class "Default")
      (node (ref "IC41") (pin "21") (pinfunction "B1_21") (pintype "bidirectional"))
    )
    (net (code "89") (name "/PLL_DAC2_SYNC_N") (class "Default")
      (node (ref "IC41") (pin "19") (pinfunction "B3_19") (pintype "bidirectional"))
    )
    (net (code "90") (name "/PLL_DAC_DIN") (class "Default")
      (node (ref "IC41") (pin "18") (pinfunction "B4_18") (pintype "bidirectional"))
    )
    (net (code "91") (name "/PLL_DAC_SCLK") (class "Default")
      (node (ref "IC41") (pin "20") (pinfunction "B2_20") (pintype "bidirectional"))
    )
    (net (code "92") (name "/PLL_VADJ2_DAC1_SYNC_N") (class "Default")
      (node (ref "IC41") (pin "5") (pinfunction "A3_5") (pintype "bidirectional"))
    )
    (net (code "93") (name "/PLL_VADJ2_DAC2_SYNC_N") (class "Default")
      (node (ref "IC41") (pin "3") (pinfunction "A1_3") (pintype "bidirectional"))
    )
    (net (code "94") (name "/PLL_VADJ2_DAC_DIN") (class "Default")
      (node (ref "IC41") (pin "6") (pinfunction "A4_6") (pintype "bidirectional"))
    )
    (net (code "95") (name "/PLL_VADJ2_DAC_SCLK") (class "Default")
      (node (ref "IC41") (pin "4") (pinfunction "A2_4") (pintype "bidirectional"))
    )
    (net (code "96") (name "/RESETn") (class "Default")
      (node (ref "IC8") (pin "1") (pinfunction "RESET_1") (pintype "input"))
    )
    (net (code "97") (name "/RTM_SYNC_CLK_N") (class "Default")
      (node (ref "C814") (pin "2") (pinfunction "2_2") (pintype "passive"))
    )
    (net (code "98") (name "/RTM_SYNC_CLK_P") (class "Default")
      (node (ref "C813") (pin "2") (pinfunction "2_2") (pintype "passive"))
    )
    (net (code "99") (name "/SI57X_CLK_C_N") (class "Default")
      (node (ref "C403") (pin "2") (pinfunction "2_2") (pintype "passive"))
      (node (ref "IC8") (pin "73") (pinfunction "IP15_73") (pintype "input"))
    )
    (net (code "100") (name "/SI57X_CLK_C_P") (class "Default")
      (node (ref "C401") (pin "2") (pinfunction "2_2") (pintype "passive"))
      (node (ref "IC8") (pin "74") (pinfunction "IN15_74") (pintype "input"))
    )
    (net (code "101") (name "/SI57X_CLK_N") (class "Default")
      (node (ref "C403") (pin "1") (pinfunction "1_1") (pintype "passive"))
    )
    (net (code "102") (name "/SI57X_CLK_P") (class "Default")
      (node (ref "C401") (pin "1") (pinfunction "1_1") (pintype "passive"))
    )
    (net (code "103") (name "/SI57X_OE") (class "Default")
      (node (ref "IC41") (pin "17") (pinfunction "B5_17") (pintype "bidirectional"))
    )
    (net (code "104") (name "/SI57X_SCL") (class "Default")
      (node (ref "IC42") (pin "7") (pinfunction "SCLB_7") (pintype "bidirectional"))
      (node (ref "R68") (pin "2") (pinfunction "2_2") (pintype "passive"))
    )
    (net (code "105") (name "/SI57X_SDA") (class "Default")
      (node (ref "IC42") (pin "6") (pinfunction "SDAB_6") (pintype "bidirectional"))
      (node (ref "R67") (pin "2") (pinfunction "2_2") (pintype "passive"))
    )
    (net (code "106") (name "/SI57X_TUNE") (class "Default")
      (node (ref "IC41") (pin "16") (pinfunction "B6_16") (pintype "bidirectional"))
    )
    (net (code "107") (name "/TCLKA_CIN_N") (class "Default")
      (node (ref "C458") (pin "2") (pinfunction "2_2") (pintype "passive"))
      (node (ref "IC8") (pin "17") (pinfunction "IP5_17") (pintype "input"))
    )
    (net (code "108") (name "/TCLKA_CIN_P") (class "Default")
      (node (ref "C414") (pin "2") (pinfunction "2_2") (pintype "passive"))
      (node (ref "IC8") (pin "18") (pinfunction "IN5_18") (pintype "input"))
    )
    (net (code "109") (name "/TCLKA_COUT_N") (class "Default")
      (node (ref "C482") (pin "1") (pinfunction "1_1") (pintype "passive"))
      (node (ref "IC8") (pin "34") (pinfunction "ON2_34") (pintype "output"))
    )
    (net (code "110") (name "/TCLKA_COUT_P") (class "Default")
      (node (ref "C480") (pin "1") (pinfunction "1_1") (pintype "passive"))
      (node (ref "IC8") (pin "33") (pinfunction "OP2_33") (pintype "output"))
    )
    (net (code "111") (name "/TCLKA_N") (class "Default")
      (node (ref "C458") (pin "1") (pinfunction "1_1") (pintype "passive"))
      (node (ref "C482") (pin "2") (pinfunction "2_2") (pintype "passive"))
    )
    (net (code "112") (name "/TCLKA_P") (class "Default")
      (node (ref "C414") (pin "1") (pinfunction "1_1") (pintype "passive"))
      (node (ref "C480") (pin "2") (pinfunction "2_2") (pintype "passive"))
    )
    (net (code "113") (name "/TCLKB_CIN_N") (class "Default")
      (node (ref "C462") (pin "2") (pinfunction "2_2") (pintype "passive"))
      (node (ref "IC8") (pin "14") (pinfunction "IP4_14") (pintype "input"))
    )
    (net (code "114") (name "/TCLKB_CIN_P") (class "Default")
      (node (ref "C460") (pin "2") (pinfunction "2_2") (pintype "passive"))
      (node (ref "IC8") (pin "15") (pinfunction "IN4_15") (pintype "input"))
    )
    (net (code "115") (name "/TCLKB_COUT_N") (class "Default")
      (node (ref "C486") (pin "1") (pinfunction "1_1") (pintype "passive"))
      (node (ref "IC8") (pin "37") (pinfunction "ON3_37") (pintype "output"))
    )
    (net (code "116") (name "/TCLKB_COUT_P") (class "Default")
      (node (ref "C484") (pin "1") (pinfunction "1_1") (pintype "passive"))
      (node (ref "IC8") (pin "36") (pinfunction "OP3_36") (pintype "output"))
    )
    (net (code "117") (name "/TCLKB_N") (class "Default")
      (node (ref "C462") (pin "1") (pinfunction "1_1") (pintype "passive"))
      (node (ref "C486") (pin "2") (pinfunction "2_2") (pintype "passive"))
    )
    (net (code "118") (name "/TCLKB_P") (class "Default")
      (node (ref "C460") (pin "1") (pinfunction "1_1") (pintype "passive"))
      (node (ref "C484") (pin "2") (pinfunction "2_2") (pintype "passive"))
    )
    (net (code "119") (name "/TCLKC_CIN_N") (class "Default")
      (node (ref "C477") (pin "2") (pinfunction "2_2") (pintype "passive"))
      (node (ref "IC8") (pin "20") (pinfunction "IP6_20") (pintype "input"))
    )
    (net (code "120") (name "/TCLKC_CIN_P") (class "Default")
      (node (ref "C464") (pin "2") (pinfunction "2_2") (pintype "passive"))
      (node (ref "IC8") (pin "21") (pinfunction "IN6_21") (pintype "input"))
    )
    (net (code "121") (name "/TCLKC_COUT_N") (class "Default")
      (node (ref "C490") (pin "1") (pinfunction "1_1") (pintype "passive"))
      (node (ref "IC8") (pin "31") (pinfunction "ON1_31") (pintype "output"))
    )
    (net (code "122") (name "/TCLKC_COUT_P") (class "Default")
      (node (ref "C488") (pin "1") (pinfunction "1_1") (pintype "passive"))
      (node (ref "IC8") (pin "30") (pinfunction "OP1_30") (pintype "output"))
    )
    (net (code "123") (name "/TCLKC_N") (class "Default")
      (node (ref "C477") (pin "1") (pinfunction "1_1") (pintype "passive"))
      (node (ref "C490") (pin "2") (pinfunction "2_2") (pintype "passive"))
    )
    (net (code "124") (name "/TCLKC_P") (class "Default")
      (node (ref "C464") (pin "1") (pinfunction "1_1") (pintype "passive"))
      (node (ref "C488") (pin "2") (pinfunction "2_2") (pintype "passive"))
    )
    (net (code "125") (name "/TCLKD_CIN_N") (class "Default")
      (node (ref "C481") (pin "2") (pinfunction "2_2") (pintype "passive"))
      (node (ref "IC8") (pin "23") (pinfunction "IP7_23") (pintype "input"))
    )
    (net (code "126") (name "/TCLKD_CIN_P") (class "Default")
      (node (ref "C479") (pin "2") (pinfunction "2_2") (pintype "passive"))
      (node (ref "IC8") (pin "24") (pinfunction "IN7_24") (pintype "input"))
    )
    (net (code "127") (name "/TCLKD_COUT_N") (class "Default")
      (node (ref "C494") (pin "1") (pinfunction "1_1") (pintype "passive"))
      (node (ref "IC8") (pin "28") (pinfunction "ON0_28") (pintype "output"))
    )
    (net (code "128") (name "/TCLKD_COUT_P") (class "Default")
      (node (ref "C492") (pin "1") (pinfunction "1_1") (pintype "passive"))
      (node (ref "IC8") (pin "27") (pinfunction "OP0_27") (pintype "output"))
    )
    (net (code "129") (name "/TCLKD_N") (class "Default")
      (node (ref "C481") (pin "1") (pinfunction "1_1") (pintype "passive"))
      (node (ref "C494") (pin "2") (pinfunction "2_2") (pintype "passive"))
    )
    (net (code "130") (name "/TCLKD_P") (class "Default")
      (node (ref "C479") (pin "1") (pinfunction "1_1") (pintype "passive"))
      (node (ref "C492") (pin "2") (pinfunction "2_2") (pintype "passive"))
    )
    (net (code "132") (name "/UPDATEn") (class "Default")
      (node (ref "R139") (pin "2") (pinfunction "2_2") (pintype "passive"))
    )
    (net (code "133") (name "/UPD_R") (class "Default")
      (node (ref "IC8") (pin "25") (pinfunction "*UPDATE_25") (pintype "passive"))
      (node (ref "R139") (pin "1") (pinfunction "1_1") (pintype "passive"))
      (node (ref "R140") (pin "1") (pinfunction "1_1") (pintype "passive"))
    )
    (net (code "134") (name "/VADJ2_CLK_UPDATEn") (class "Default")
      (node (ref "IC41") (pin "9") (pinfunction "A7_9") (pintype "bidirectional"))
    )
    (net (code "135") (name "/VADJ2_SI57X_OE") (class "Default")
      (node (ref "IC41") (pin "7") (pinfunction "A5_7") (pintype "bidirectional"))
    )
    (net (code "136") (name "/VADJ2_SI57X_SCL") (class "Default")
      (node (ref "IC42") (pin "2") (pinfunction "SCLA_2") (pintype "bidirectional"))
      (node (ref "R271") (pin "2") (pinfunction "2_2") (pintype "passive"))
    )
    (net (code "137") (name "/VADJ2_SI57X_SDA") (class "Default")
      (node (ref "IC42") (pin "3") (pinfunction "SDAA_3") (pintype "bidirectional"))
      (node (ref "R214") (pin "2") (pinfunction "2_2") (pintype "passive"))
    )
    (net (code "138") (name "/VADJ2_SI57X_TUNE") (class "Default")
      (node (ref "IC41") (pin "8") (pinfunction "A6_8") (pintype "bidirectional"))
    )
    (net (code "139") (name "/VTTI") (class "Default")
      (node (ref "C571") (pin "1") (pinfunction "1_1") (pintype "passive"))
      (node (ref "C572") (pin "1") (pinfunction "1_1") (pintype "passive"))
      (node (ref "C573") (pin "1") (pinfunction "1_1") (pintype "passive"))
      (node (ref "C574") (pin "1") (pinfunction "1_1") (pintype "passive"))
      (node (ref "IC8") (pin "19") (pinfunction "VTTIW_19") (pintype "passive"))
      (node (ref "IC8") (pin "57") (pinfunction "VTTIE_57") (pintype "passive"))
      (node (ref "IC8") (pin "69") (pinfunction "VTTIE_69") (pintype "passive"))
      (node (ref "IC8") (pin "7") (pinfunction "VTTIW_7") (pintype "passive"))
      (node (ref "L19") (pin "1") (pinfunction "1_1") (pintype "passive"))
    )
    (net (code "140") (name "/VTTO") (class "Default")
      (node (ref "C567") (pin "2") (pinfunction "2_2") (pintype "passive"))
      (node (ref "C568") (pin "2") (pinfunction "2_2") (pintype "passive"))
      (node (ref "C569") (pin "2") (pinfunction "2_2") (pintype "passive"))
      (node (ref "C570") (pin "2") (pinfunction "2_2") (pintype "passive"))
      (node (ref "IC8") (pin "32") (pinfunction "VTTOS_32") (pintype "passive"))
      (node (ref "IC8") (pin "44") (pinfunction "VTTOS_44") (pintype "passive"))
      (node (ref "IC8") (pin "82") (pinfunction "VTTON_82") (pintype "passive"))
      (node (ref "IC8") (pin "94") (pinfunction "VTTON_94") (pintype "passive"))
      (node (ref "L18") (pin "1") (pinfunction "1_1") (pintype "passive"))
    )
    (net (code "141") (name "/WR_PLL_CLK1_C_N") (class "Default")
      (node (ref "C399") (pin "2") (pinfunction "2_2") (pintype "passive"))
      (node (ref "IC8") (pin "68") (pinfunction "IN13_68") (pintype "input"))
    )
    (net (code "142") (name "/WR_PLL_CLK1_C_P") (class "Default")
      (node (ref "C397") (pin "2") (pinfunction "2_2") (pintype "passive"))
      (node (ref "IC8") (pin "67") (pinfunction "IP13_67") (pintype "input"))
    )
    (net (code "143") (name "/WR_PLL_CLK1_N") (class "Default")
      (node (ref "C399") (pin "1") (pinfunction "1_1") (pintype "passive"))
    )
    (net (code "144") (name "/WR_PLL_CLK1_P") (class "Default")
      (node (ref "C397") (pin "1") (pinfunction "1_1") (pintype "passive"))
    )
    (net (code "152") (name "GND") (class "Default")
      (node (ref "C128") (pin "1") (pinfunction "1_1") (pintype "passive"))
      (node (ref "C389") (pin "1") (pinfunction "1_1") (pintype "passive"))
      (node (ref "C391") (pin "1") (pinfunction "1_1") (pintype "passive"))
      (node (ref "C408") (pin "1") (pinfunction "1_1") (pintype "passive"))
      (node (ref "C412") (pin "1") (pinfunction "1_1") (pintype "passive"))
      (node (ref "C454") (pin "1") (pinfunction "1_1") (pintype "passive"))
      (node (ref "C515") (pin "1") (pinfunction "1_1") (pintype "passive"))
      (node (ref "C516") (pin "1") (pinfunction "1_1") (pintype "passive"))
      (node (ref "C517") (pin "1") (pinfunction "1_1") (pintype "passive"))
      (node (ref "C518") (pin "1") (pinfunction "1_1") (pintype "passive"))
      (node (ref "C519") (pin "1") (pinfunction "1_1") (pintype "passive"))
      (node (ref "C520") (pin "1") (pinfunction "1_1") (pintype "passive"))
      (node (ref "C521") (pin "1") (pinfunction "1_1") (pintype "passive"))
      (node (ref "C522") (pin "1") (pinfunction "1_1") (pintype "passive"))
      (node (ref "C523") (pin "1") (pinfunction "1_1") (pintype "passive"))
      (node (ref "C524") (pin "1") (pinfunction "1_1") (pintype "passive"))
      (node (ref "C567") (pin "1") (pinfunction "1_1") (pintype "passive"))
      (node (ref "C568") (pin "1") (pinfunction "1_1") (pintype "passive"))
      (node (ref "C569") (pin "1") (pinfunction "1_1") (pintype "passive"))
      (node (ref "C570") (pin "1") (pinfunction "1_1") (pintype "passive"))
      (node (ref "C571") (pin "2") (pinfunction "2_2") (pintype "passive"))
      (node (ref "C572") (pin "2") (pinfunction "2_2") (pintype "passive"))
      (node (ref "C573") (pin "2") (pinfunction "2_2") (pintype "passive"))
      (node (ref "C574") (pin "2") (pinfunction "2_2") (pintype "passive"))
      (node (ref "C762") (pin "2") (pinfunction "2_2") (pintype "passive"))
      (node (ref "C766") (pin "2") (pinfunction "2_2") (pintype "passive"))
      (node (ref "CC524") (pin "1") (pinfunction "1_1") (pintype "passive"))
      (node (ref "IC41") (pin "10") (pinfunction "A8_10") (pintype "bidirectional"))
      (node (ref "IC41") (pin "11") (pinfunction "GND_11") (pintype "power_in"))
      (node (ref "IC41") (pin "12") (pinfunction "GND_12") (pintype "power_in"))
      (node (ref "IC41") (pin "13") (pinfunction "GND_13") (pintype "power_in"))
      (node (ref "IC41") (pin "22") (pinfunction "~{OE}_22") (pintype "input"))
      (node (ref "IC41") (pin "25") (pinfunction "GND_25") (pintype "power_in"))
      (node (ref "IC42") (pin "4") (pinfunction "GND_4") (pintype "power_in"))
      (node (ref "IC56") (pin "1") (pinfunction "GND_1") (pintype "power_in"))
      (node (ref "IC8") (pin "0") (pinfunction "EP(VEE)_0") (pintype "power_in"))
      (node (ref "IC8") (pin "10") (pinfunction "VEE_10") (pintype "power_in"))
      (node (ref "IC8") (pin "16") (pinfunction "VEE_16") (pintype "power_in"))
      (node (ref "IC8") (pin "29") (pinfunction "VEE_29") (pintype "power_in"))
      (node (ref "IC8") (pin "38") (pinfunction "VEE_38") (pintype "power_in"))
      (node (ref "IC8") (pin "47") (pinfunction "VEE_47") (pintype "power_in"))
      (node (ref "IC8") (pin "60") (pinfunction "VEE_60") (pintype "power_in"))
      (node (ref "IC8") (pin "66") (pinfunction "VEE_66") (pintype "power_in"))
      (node (ref "IC8") (pin "79") (pinfunction "VEE_79") (pintype "power_in"))
      (node (ref "IC8") (pin "88") (pinfunction "VEE_88") (pintype "power_in"))
      (node (ref "IC8") (pin "97") (pinfunction "VEE_97") (pintype "power_in"))
      (node (ref "J11") (pin "2") (pintype "passive"))
      (node (ref "J11") (pin "2a") (pinfunction "GND_2a") (pintype "passive"))
      (node (ref "J7") (pin "2") (pintype "passive"))
      (node (ref "J7") (pin "2a") (pinfunction "GND_2a") (pintype "passive"))
      (node (ref "R146") (pin "2") (pinfunction "2_2") (pintype "passive"))
    )
    (net (code "153") (name "Net-(IC8B-ON12)") (class "Default")
      (node (ref "C814") (pin "1") (pinfunction "1_1") (pintype "passive"))
      (node (ref "IC8") (pin "90") (pinfunction "ON12_90") (pintype "output"))
    )
    (net (code "154") (name "Net-(IC8B-OP12)") (class "Default")
      (node (ref "C813") (pin "1") (pinfunction "1_1") (pintype "passive"))
      (node (ref "IC8") (pin "89") (pinfunction "OP12_89") (pintype "output"))
    )
    (net (code "155") (name "Net-(IC56-EN)") (class "Default")
      (node (ref "C762") (pin "1") (pinfunction "1_1") (pintype "passive"))
      (node (ref "IC56") (pin "7") (pinfunction "VREF2_7") (pintype "input"))
      (node (ref "IC56") (pin "8") (pinfunction "EN_8") (pintype "input"))
      (node (ref "R52") (pin "2") (pinfunction "2_2") (pintype "passive"))
    )
    (net (code "156") (name "P3V3") (class "Default")
      (node (ref "C389") (pin "2") (pinfunction "2_2") (pintype "passive"))
      (node (ref "C391") (pin "2") (pinfunction "2_2") (pintype "passive"))
      (node (ref "IC41") (pin "23") (pinfunction "VCCB_23") (pintype "power_in"))
      (node (ref "IC41") (pin "24") (pinfunction "VCCB_24") (pintype "power_in"))
      (node (ref "IC42") (pin "5") (pinfunction "EN_5") (pintype "input"))
      (node (ref "IC42") (pin "8") (pinfunction "Vccb_8") (pintype "power_in"))
      (node (ref "L11") (pin "1") (pintype "passive"))
      (node (ref "R313") (pin "2") (pinfunction "2_2") (pintype "passive"))
      (node (ref "R314") (pin "2") (pinfunction "2_2") (pintype "passive"))
      (node (ref "R52") (pin "1") (pinfunction "1_1") (pintype "passive"))
    )
    (net (code "157") (name "P3V3MP") (class "Default")
      (node (ref "C766") (pin "1") (pinfunction "1_1") (pintype "passive"))
      (node (ref "IC56") (pin "2") (pinfunction "VREF1_2") (pintype "input"))
    )
    (net (code "158") (name "P3V3_CLKSW") (class "Default")
      (node (ref "C454") (pin "2") (pinfunction "2_2") (pintype "passive"))
      (node (ref "C515") (pin "2") (pinfunction "2_2") (pintype "passive"))
      (node (ref "C516") (pin "2") (pinfunction "2_2") (pintype "passive"))
      (node (ref "C517") (pin "2") (pinfunction "2_2") (pintype "passive"))
      (node (ref "C518") (pin "2") (pinfunction "2_2") (pintype "passive"))
      (node (ref "C519") (pin "2") (pinfunction "2_2") (pintype "passive"))
      (node (ref "C520") (pin "2") (pinfunction "2_2") (pintype "passive"))
      (node (ref "C521") (pin "2") (pinfunction "2_2") (pintype "passive"))
      (node (ref "C522") (pin "2") (pinfunction "2_2") (pintype "passive"))
      (node (ref "C523") (pin "2") (pinfunction "2_2") (pintype "passive"))
      (node (ref "C524") (pin "2") (pinfunction "2_2") (pintype "passive"))
      (node (ref "CC524") (pin "2") (pinfunction "2_2") (pintype "passive"))
      (node (ref "IC8") (pin "100") (pinfunction "DVCC_100") (pintype "power_in"))
      (node (ref "IC8") (pin "13") (pinfunction "VCC_13") (pintype "power_in"))
      (node (ref "IC8") (pin "22") (pinfunction "VCC_22") (pintype "power_in"))
      (node (ref "IC8") (pin "35") (pinfunction "VCC_35") (pintype "power_in"))
      (node (ref "IC8") (pin "4") (pinfunction "VCC_4") (pintype "power_in"))
      (node (ref "IC8") (pin "41") (pinfunction "VCC_41") (pintype "power_in"))
      (node (ref "IC8") (pin "54") (pinfunction "VCC_54") (pintype "power_in"))
      (node (ref "IC8") (pin "63") (pinfunction "VCC_63") (pintype "power_in"))
      (node (ref "IC8") (pin "72") (pinfunction "VCC_72") (pintype "power_in"))
      (node (ref "IC8") (pin "85") (pinfunction "VCC_85") (pintype "power_in"))
      (node (ref "IC8") (pin "91") (pinfunction "VCC_91") (pintype "power_in"))
      (node (ref "L11") (pin "2") (pintype "passive"))
      (node (ref "L18") (pin "2") (pinfunction "2_2") (pintype "passive"))
      (node (ref "L19") (pin "2") (pinfunction "2_2") (pintype "passive"))
      (node (ref "R141") (pin "2") (pinfunction "2_2") (pintype "passive"))
      (node (ref "R145") (pin "2") (pinfunction "2_2") (pintype "passive"))
    )
    (net (code "159") (name "PVADJ2") (class "Default")
      (node (ref "C128") (pin "2") (pinfunction "2_2") (pintype "passive"))
      (node (ref "C408") (pin "2") (pinfunction "2_2") (pintype "passive"))
      (node (ref "IC41") (pin "1") (pinfunction "VCCA_1") (pintype "power_in"))
      (node (ref "IC41") (pin "2") (pinfunction "DIR_2") (pintype "input"))
      (node (ref "IC42") (pin "1") (pinfunction "Vcca_1") (pintype "power_in"))
      (node (ref "R214") (pin "1") (pinfunction "1_1") (pintype "passive"))
      (node (ref "R271") (pin "1") (pinfunction "1_1") (pintype "passive"))
    )
    (net (code "160") (name "unconnected-(IC41-B8-Pad14)") (class "Default")
      (node (ref "IC41") (pin "14") (pinfunction "B8_14") (pintype "bidirectional"))
    )
    (net (code "161") (name "unconnected-(IC56-SCL1-Pad3)") (class "Default")
      (node (ref "IC56") (pin "3") (pinfunction "SCL1_3") (pintype "bidirectional"))
    )
    (net (code "162") (name "unconnected-(IC56-SDA1-Pad4)") (class "Default")
      (node (ref "IC56") (pin "4") (pinfunction "SDA1_4") (pintype "bidirectional"))
    )
  )
)
